# impulse.net
KiCad netlist of a schematic drawn in EAGLE
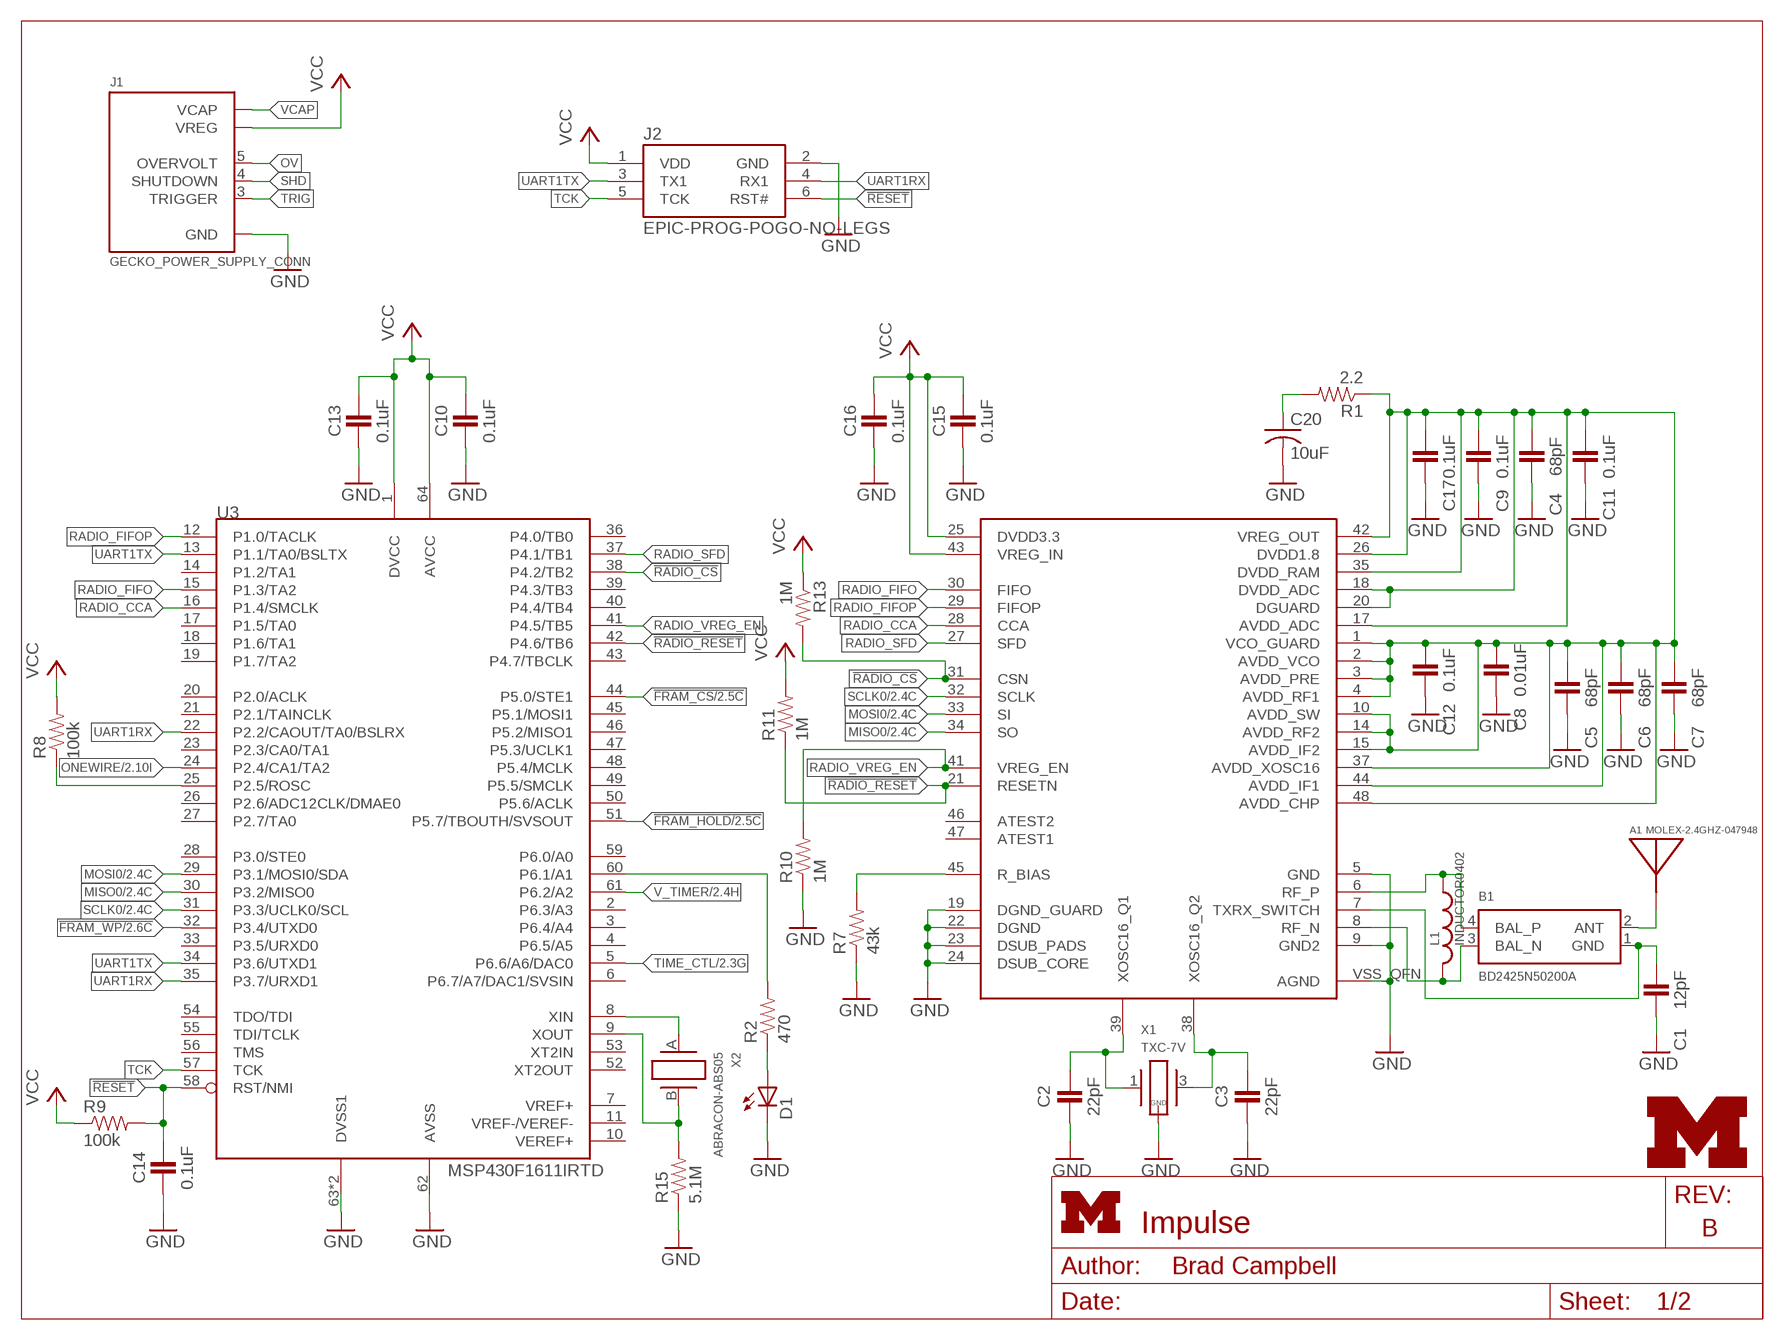
[diagram p0: schematic, sheet 1]
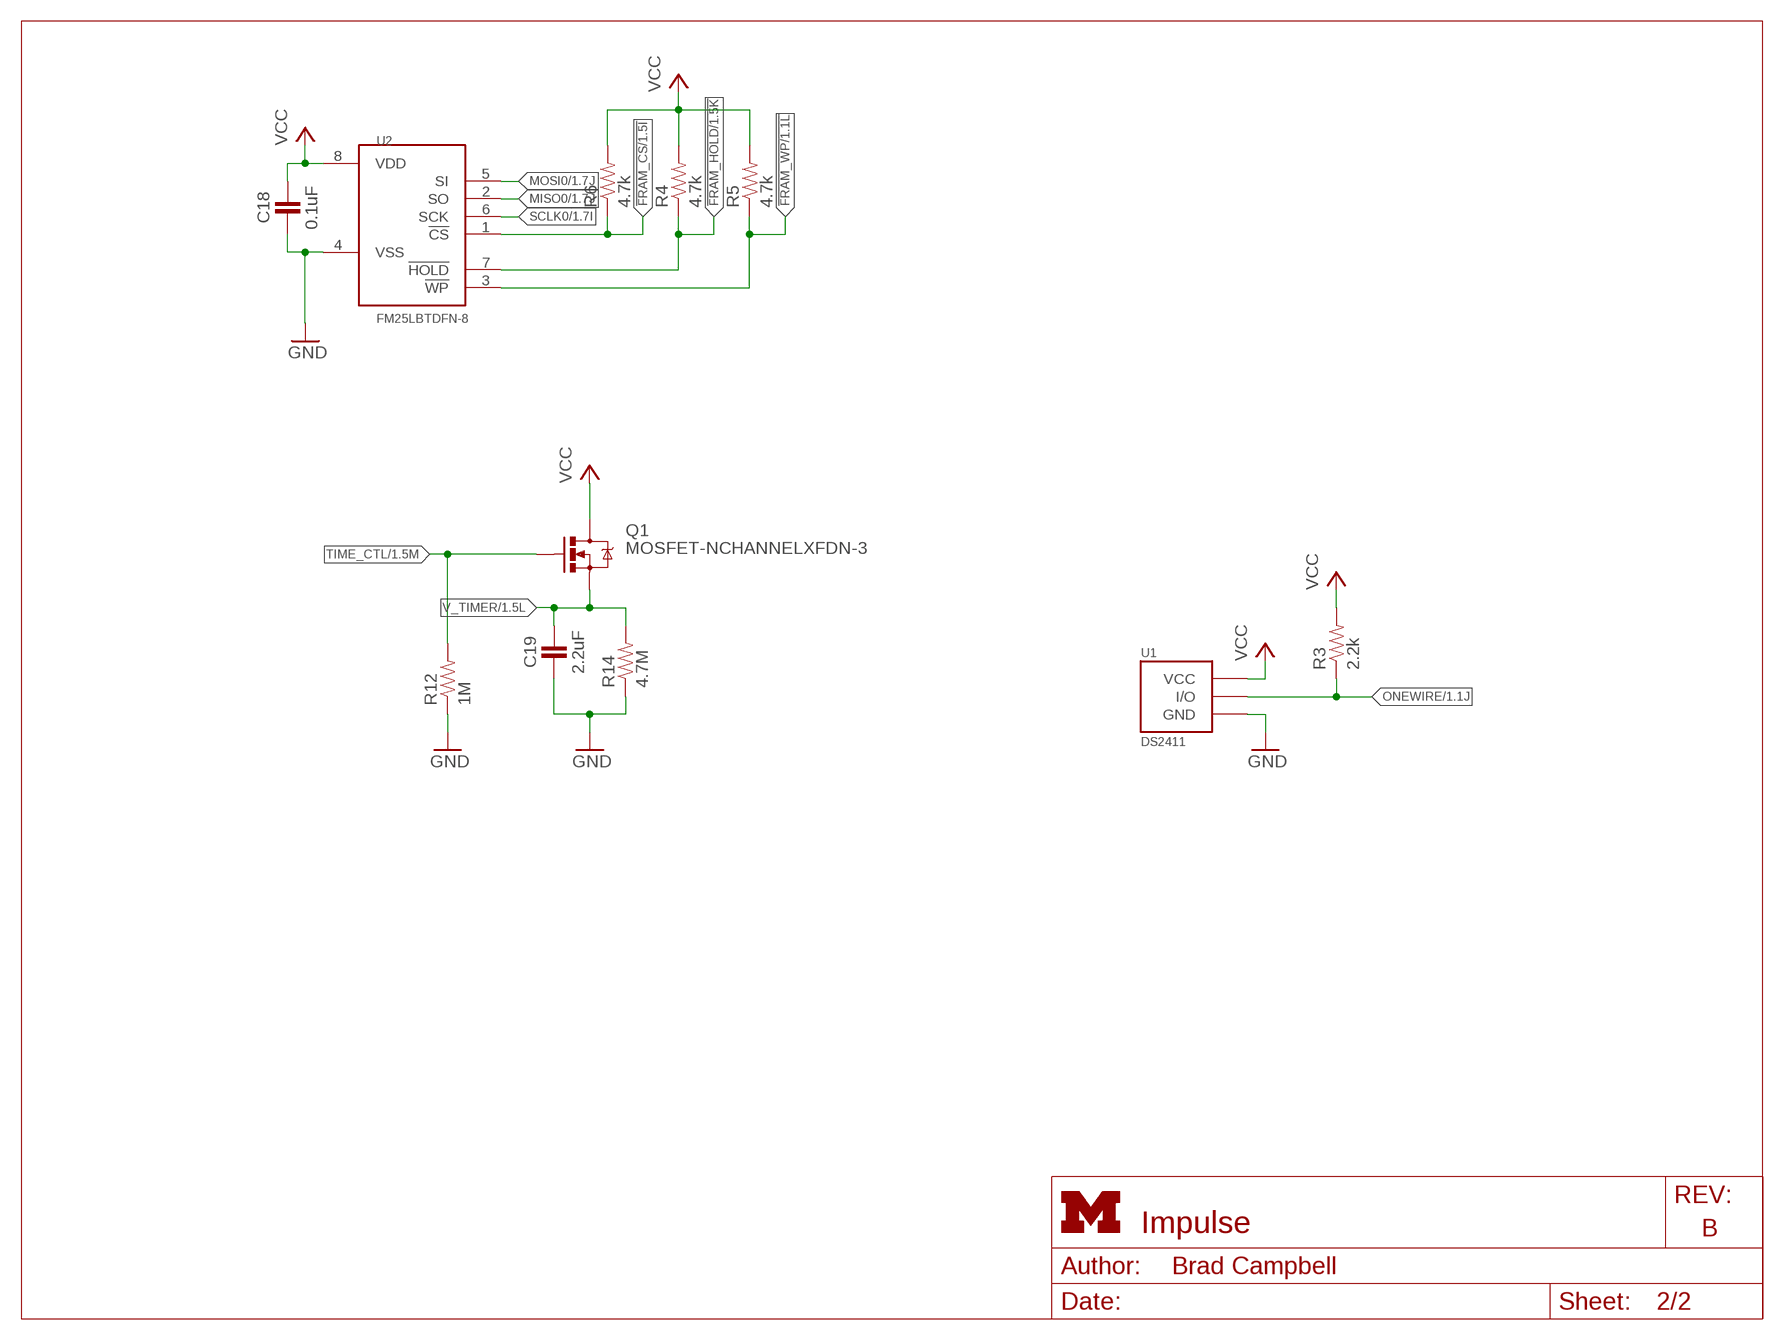
[diagram p1: schematic, sheet 2]

(export (version "E")
  (design (tool "Eeschema 10.0.6"))
  (components
    (comp (ref "C18")
      (value "0.1uF")
      (footprint "eagle-import:0402_CAP")
      (libsource (lib "eagle-import") (part "CAPACITOR"))
    )
    (comp (ref "C19")
      (value "2.2uF")
      (footprint "eagle-import:0402_CAP")
      (libsource (lib "eagle-import") (part "CAPACITOR"))
    )
    (comp (ref "Q1")
      (value "MOSFET-NCHANNELXFDN-3")
      (footprint "eagle-import:XFDFN-3")
      (libsource (lib "eagle-import") (part "MOSFET-NCHANNELXFDN-3"))
    )
    (comp (ref "R3")
      (value "2.2k")
      (footprint "eagle-import:0402_RES")
      (libsource (lib "eagle-import") (part "RESISTOR"))
    )
    (comp (ref "R4")
      (value "4.7k")
      (footprint "eagle-import:0402_RES")
      (libsource (lib "eagle-import") (part "RESISTOR"))
    )
    (comp (ref "R5")
      (value "4.7k")
      (footprint "eagle-import:0402_RES")
      (libsource (lib "eagle-import") (part "RESISTOR"))
    )
    (comp (ref "R6")
      (value "4.7k")
      (footprint "eagle-import:0402_RES")
      (libsource (lib "eagle-import") (part "RESISTOR"))
    )
    (comp (ref "R12")
      (value "1M")
      (footprint "eagle-import:0402_RES")
      (libsource (lib "eagle-import") (part "RESISTOR"))
    )
    (comp (ref "R14")
      (value "4.7M")
      (footprint "eagle-import:0402_RES")
      (libsource (lib "eagle-import") (part "RESISTOR"))
    )
    (comp (ref "U1")
      (value "DS2411")
      (footprint "eagle-import:SOT-23")
      (libsource (lib "eagle-import") (part "DS2411"))
    )
    (comp (ref "U2")
      (value "FM25LBTDFN-8")
      (footprint "eagle-import:TDFN-8")
      (libsource (lib "eagle-import") (part "FM25LBTDFN-8"))
    )
    (comp (ref "A1")
      (value "MOLEX-2.4GHZ-047948")
      (footprint "eagle-import:MOLEX-47948-ANTENNA")
      (libsource (lib "eagle-import") (part "MOLEX-2.4GHZ-047948"))
    )
    (comp (ref "B1")
      (value "BD2425N50200A")
      (footprint "eagle-import:BD2425N50200A")
      (libsource (lib "eagle-import") (part "BD2425N50200A"))
    )
    (comp (ref "C1")
      (value "12pF")
      (footprint "eagle-import:0402_CAP")
      (libsource (lib "eagle-import") (part "CAPACITOR"))
    )
    (comp (ref "C2")
      (value "22pF")
      (footprint "eagle-import:0402_CAP")
      (libsource (lib "eagle-import") (part "CAPACITOR"))
    )
    (comp (ref "C3")
      (value "22pF")
      (footprint "eagle-import:0402_CAP")
      (libsource (lib "eagle-import") (part "CAPACITOR"))
    )
    (comp (ref "C4")
      (value "68pF")
      (footprint "eagle-import:0402_CAP")
      (libsource (lib "eagle-import") (part "CAPACITOR"))
    )
    (comp (ref "C5")
      (value "68pF")
      (footprint "eagle-import:0402_CAP")
      (libsource (lib "eagle-import") (part "CAPACITOR"))
    )
    (comp (ref "C6")
      (value "68pF")
      (footprint "eagle-import:0402_CAP")
      (libsource (lib "eagle-import") (part "CAPACITOR"))
    )
    (comp (ref "C7")
      (value "68pF")
      (footprint "eagle-import:0402_CAP")
      (libsource (lib "eagle-import") (part "CAPACITOR"))
    )
    (comp (ref "C8")
      (value "0.01uF")
      (footprint "eagle-import:0402_CAP")
      (libsource (lib "eagle-import") (part "CAPACITOR"))
    )
    (comp (ref "C9")
      (value "0.1uF")
      (footprint "eagle-import:0402_CAP")
      (libsource (lib "eagle-import") (part "CAPACITOR"))
    )
    (comp (ref "C10")
      (value "0.1uF")
      (footprint "eagle-import:0402_CAP")
      (libsource (lib "eagle-import") (part "CAPACITOR"))
    )
    (comp (ref "C11")
      (value "0.1uF")
      (footprint "eagle-import:0402_CAP")
      (libsource (lib "eagle-import") (part "CAPACITOR"))
    )
    (comp (ref "C12")
      (value "0.1uF")
      (footprint "eagle-import:0402_CAP")
      (libsource (lib "eagle-import") (part "CAPACITOR"))
    )
    (comp (ref "C13")
      (value "0.1uF")
      (footprint "eagle-import:0402_CAP")
      (libsource (lib "eagle-import") (part "CAPACITOR"))
    )
    (comp (ref "C14")
      (value "0.1uF")
      (footprint "eagle-import:0402_CAP")
      (libsource (lib "eagle-import") (part "CAPACITOR"))
    )
    (comp (ref "C15")
      (value "0.1uF")
      (footprint "eagle-import:0402_CAP")
      (libsource (lib "eagle-import") (part "CAPACITOR"))
    )
    (comp (ref "C16")
      (value "0.1uF")
      (footprint "eagle-import:0402_CAP")
      (libsource (lib "eagle-import") (part "CAPACITOR"))
    )
    (comp (ref "C17")
      (value "0.1uF")
      (footprint "eagle-import:0402_CAP")
      (libsource (lib "eagle-import") (part "CAPACITOR"))
    )
    (comp (ref "C20")
      (value "10uF")
      (footprint "eagle-import:C0805")
      (libsource (lib "eagle-import") (part "C-USC0805"))
    )
    (comp (ref "D1")
      (value "LED0603")
      (footprint "eagle-import:LED-0603")
      (libsource (lib "eagle-import") (part "LED0603"))
    )
    (comp (ref "J1")
      (value "GECKO_POWER_SUPPLY_CONN")
      (footprint "eagle-import:HEADER1X6_0.05IN")
      (libsource (lib "eagle-import") (part "GECKO_POWER_SUPPLY_CONN"))
    )
    (comp (ref "J2")
      (value "EPIC-PROG-POGO-NO-LEGS")
      (footprint "eagle-import:TC2030-IDC-NL")
      (libsource (lib "eagle-import") (part "EPIC-PROG-POGO-NO-LEGS"))
    )
    (comp (ref "L1")
      (value "INDUCTOR0402")
      (footprint "eagle-import:0402_CAP")
      (libsource (lib "eagle-import") (part "INDUCTOR0402"))
    )
    (comp (ref "R1")
      (value "2.2")
      (footprint "eagle-import:0402_RES")
      (libsource (lib "eagle-import") (part "RESISTOR"))
    )
    (comp (ref "R2")
      (value "470")
      (footprint "eagle-import:0402_RES")
      (libsource (lib "eagle-import") (part "RESISTOR"))
    )
    (comp (ref "R7")
      (value "43k")
      (footprint "eagle-import:0402_RES")
      (libsource (lib "eagle-import") (part "RESISTOR"))
    )
    (comp (ref "R8")
      (value "100k")
      (footprint "eagle-import:0402_RES")
      (libsource (lib "eagle-import") (part "RESISTOR"))
    )
    (comp (ref "R9")
      (value "100k")
      (footprint "eagle-import:0402_RES")
      (libsource (lib "eagle-import") (part "RESISTOR"))
    )
    (comp (ref "R10")
      (value "1M")
      (footprint "eagle-import:0402_RES")
      (libsource (lib "eagle-import") (part "RESISTOR"))
    )
    (comp (ref "R11")
      (value "1M")
      (footprint "eagle-import:0402_RES")
      (libsource (lib "eagle-import") (part "RESISTOR"))
    )
    (comp (ref "R13")
      (value "1M")
      (footprint "eagle-import:0402_RES")
      (libsource (lib "eagle-import") (part "RESISTOR"))
    )
    (comp (ref "R15")
      (value "5.1M")
      (footprint "eagle-import:0402_RES")
      (libsource (lib "eagle-import") (part "RESISTOR"))
    )
    (comp (ref "U$1")
      (value "UMICH_SOLID_SMALL")
      (footprint "eagle-import:UMICH_SOLID_75MIL")
      (libsource (lib "eagle-import") (part "UMICH_SOLID_SMALL"))
    )
    (comp (ref "U3")
      (value "MSP430F1611IRTD")
      (footprint "eagle-import:S-PVQFN-N64")
      (libsource (lib "eagle-import") (part "MSP430F1611IRTD"))
    )
    (comp (ref "U4")
      (value "CC2420RGZ")
      (footprint "eagle-import:S-PVQFN-N48")
      (libsource (lib "eagle-import") (part "CC2420RGZ"))
    )
    (comp (ref "X1")
      (value "TXC-7V")
      (footprint "eagle-import:TXC-7V")
      (libsource (lib "eagle-import") (part "TXC-7V"))
    )
    (comp (ref "X2")
      (value "ABRACON-ABS05")
      (footprint "eagle-import:ABS05")
      (libsource (lib "eagle-import") (part "ABRACON-ABS05"))
    )
  )
  (nets
    (net (code "1") (name "GND") (class "Default")
      (node (ref "C1") (pin "2") (pinfunction "2_2") (pintype "bidirectional"))
      (node (ref "C10") (pin "2") (pinfunction "2_2") (pintype "bidirectional"))
      (node (ref "C11") (pin "2") (pinfunction "2_2") (pintype "bidirectional"))
      (node (ref "C12") (pin "2") (pinfunction "2_2") (pintype "bidirectional"))
      (node (ref "C13") (pin "2") (pinfunction "2_2") (pintype "bidirectional"))
      (node (ref "C14") (pin "2") (pinfunction "2_2") (pintype "bidirectional"))
      (node (ref "C15") (pin "2") (pinfunction "2_2") (pintype "bidirectional"))
      (node (ref "C16") (pin "2") (pinfunction "2_2") (pintype "bidirectional"))
      (node (ref "C17") (pin "2") (pinfunction "2_2") (pintype "bidirectional"))
      (node (ref "C18") (pin "2") (pinfunction "2_2") (pintype "bidirectional"))
      (node (ref "C19") (pin "2") (pinfunction "2_2") (pintype "bidirectional"))
      (node (ref "C2") (pin "2") (pinfunction "2_2") (pintype "bidirectional"))
      (node (ref "C20") (pin "2") (pinfunction "2_2") (pintype "passive"))
      (node (ref "C3") (pin "2") (pinfunction "2_2") (pintype "bidirectional"))
      (node (ref "C4") (pin "2") (pinfunction "2_2") (pintype "bidirectional"))
      (node (ref "C5") (pin "2") (pinfunction "2_2") (pintype "bidirectional"))
      (node (ref "C6") (pin "2") (pinfunction "2_2") (pintype "bidirectional"))
      (node (ref "C7") (pin "2") (pinfunction "2_2") (pintype "bidirectional"))
      (node (ref "C8") (pin "2") (pinfunction "2_2") (pintype "bidirectional"))
      (node (ref "C9") (pin "2") (pinfunction "2_2") (pintype "bidirectional"))
      (node (ref "D1") (pin "C") (pinfunction "C_C") (pintype "passive"))
      (node (ref "J1") (pin "1") (pinfunction "GND_1") (pintype "bidirectional"))
      (node (ref "J2") (pin "2") (pinfunction "GND_2") (pintype "bidirectional"))
      (node (ref "R10") (pin "1") (pinfunction "1_1") (pintype "passive"))
      (node (ref "R12") (pin "1") (pinfunction "1_1") (pintype "passive"))
      (node (ref "R14") (pin "1") (pinfunction "1_1") (pintype "passive"))
      (node (ref "R15") (pin "1") (pinfunction "1_1") (pintype "passive"))
      (node (ref "R7") (pin "1") (pinfunction "1_1") (pintype "passive"))
      (node (ref "U1") (pin "3") (pinfunction "GND_3") (pintype "bidirectional"))
      (node (ref "U2") (pin "4") (pinfunction "VSS_4") (pintype "bidirectional"))
      (node (ref "U3") (pin "62") (pinfunction "AVSS_62") (pintype "power_in"))
      (node (ref "U3") (pin "63") (pinfunction "DVSS1_63") (pintype "power_in"))
      (node (ref "U3") (pin "GND") (pinfunction "DVSS1_GND") (pintype "power_in"))
      (node (ref "U4") (pin "19") (pinfunction "DGND_GUARD_19") (pintype "bidirectional"))
      (node (ref "U4") (pin "22") (pinfunction "DGND_22") (pintype "bidirectional"))
      (node (ref "U4") (pin "23") (pinfunction "DSUB_PADS_23") (pintype "bidirectional"))
      (node (ref "U4") (pin "24") (pinfunction "DSUB_CORE_24") (pintype "bidirectional"))
      (node (ref "U4") (pin "5") (pinfunction "GND_5") (pintype "bidirectional"))
      (node (ref "U4") (pin "9") (pinfunction "GND2_9") (pintype "bidirectional"))
      (node (ref "U4") (pin "VSS_QFN") (pinfunction "AGND_VSS_QFN") (pintype "bidirectional"))
      (node (ref "X1") (pin "2") (pinfunction "GND_2") (pintype "bidirectional"))
      (node (ref "X1") (pin "4") (pinfunction "GND_4") (pintype "bidirectional"))
    )
    (net (code "2") (name "MISO0") (class "Default")
      (node (ref "U2") (pin "2") (pinfunction "SO_2") (pintype "bidirectional"))
      (node (ref "U3") (pin "30") (pinfunction "P3.2/MISO0_30") (pintype "bidirectional"))
      (node (ref "U4") (pin "34") (pinfunction "SO_34") (pintype "bidirectional"))
    )
    (net (code "3") (name "MOSI0") (class "Default")
      (node (ref "U2") (pin "5") (pinfunction "SI_5") (pintype "bidirectional"))
      (node (ref "U3") (pin "29") (pinfunction "P3.1/MOSI0/SDA_29") (pintype "bidirectional"))
      (node (ref "U4") (pin "33") (pinfunction "SI_33") (pintype "bidirectional"))
    )
    (net (code "4") (name "Net-(A1-ANTENNA)") (class "Default")
      (node (ref "A1") (pin "1") (pinfunction "ANTENNA_1") (pintype "bidirectional"))
      (node (ref "B1") (pin "2") (pinfunction "ANT_2") (pintype "bidirectional"))
    )
    (net (code "5") (name "Net-(B1-BAL_N)") (class "Default")
      (node (ref "B1") (pin "3") (pinfunction "BAL_N_3") (pintype "bidirectional"))
      (node (ref "L1") (pin "2") (pinfunction "P$2_2") (pintype "bidirectional"))
      (node (ref "U4") (pin "8") (pinfunction "RF_N_8") (pintype "bidirectional"))
    )
    (net (code "6") (name "Net-(B1-BAL_P)") (class "Default")
      (node (ref "B1") (pin "4") (pinfunction "BAL_P_4") (pintype "bidirectional"))
      (node (ref "L1") (pin "1") (pinfunction "1_1") (pintype "bidirectional"))
      (node (ref "U4") (pin "6") (pinfunction "RF_P_6") (pintype "bidirectional"))
    )
    (net (code "7") (name "Net-(B1-GND)") (class "Default")
      (node (ref "B1") (pin "1") (pinfunction "GND_1") (pintype "bidirectional"))
      (node (ref "C1") (pin "1") (pinfunction "1_1") (pintype "bidirectional"))
      (node (ref "U4") (pin "7") (pinfunction "TXRX_SWITCH_7") (pintype "bidirectional"))
    )
    (net (code "8") (name "Net-(C20-Pad1)") (class "Default")
      (node (ref "C20") (pin "1") (pinfunction "1_1") (pintype "passive"))
      (node (ref "R1") (pin "2") (pinfunction "2_2") (pintype "passive"))
    )
    (net (code "9") (name "Net-(D1-PadA)") (class "Default")
      (node (ref "D1") (pin "A") (pinfunction "A_A") (pintype "passive"))
      (node (ref "R2") (pin "1") (pinfunction "1_1") (pintype "passive"))
    )
    (net (code "10") (name "Net-(U3-P2.5{slash}ROSC)") (class "Default")
      (node (ref "R8") (pin "1") (pinfunction "1_1") (pintype "passive"))
      (node (ref "U3") (pin "25") (pinfunction "P2.5/ROSC_25") (pintype "bidirectional"))
    )
    (net (code "11") (name "Net-(U3-P6.1{slash}A1)") (class "Default")
      (node (ref "R2") (pin "2") (pinfunction "2_2") (pintype "passive"))
      (node (ref "U3") (pin "60") (pinfunction "P6.1/A1_60") (pintype "bidirectional"))
    )
    (net (code "12") (name "Net-(U3-XIN)") (class "Default")
      (node (ref "U3") (pin "8") (pinfunction "XIN_8") (pintype "bidirectional"))
      (node (ref "X2") (pin "A") (pinfunction "1_A") (pintype "bidirectional"))
    )
    (net (code "13") (name "Net-(U3-XOUT)") (class "Default")
      (node (ref "R15") (pin "2") (pinfunction "2_2") (pintype "passive"))
      (node (ref "U3") (pin "9") (pinfunction "XOUT_9") (pintype "bidirectional"))
      (node (ref "X2") (pin "B") (pinfunction "2_B") (pintype "bidirectional"))
    )
    (net (code "14") (name "Net-(U4-AVDD_ADC)") (class "Default")
      (node (ref "C11") (pin "1") (pinfunction "1_1") (pintype "bidirectional"))
      (node (ref "C12") (pin "1") (pinfunction "1_1") (pintype "bidirectional"))
      (node (ref "C17") (pin "1") (pinfunction "1_1") (pintype "bidirectional"))
      (node (ref "C4") (pin "1") (pinfunction "1_1") (pintype "bidirectional"))
      (node (ref "C5") (pin "1") (pinfunction "1_1") (pintype "bidirectional"))
      (node (ref "C6") (pin "1") (pinfunction "1_1") (pintype "bidirectional"))
      (node (ref "C7") (pin "1") (pinfunction "1_1") (pintype "bidirectional"))
      (node (ref "C8") (pin "1") (pinfunction "1_1") (pintype "bidirectional"))
      (node (ref "C9") (pin "1") (pinfunction "1_1") (pintype "bidirectional"))
      (node (ref "R1") (pin "1") (pinfunction "1_1") (pintype "passive"))
      (node (ref "U4") (pin "1") (pinfunction "VCO_GUARD_1") (pintype "bidirectional"))
      (node (ref "U4") (pin "10") (pinfunction "AVDD_SW_10") (pintype "bidirectional"))
      (node (ref "U4") (pin "14") (pinfunction "AVDD_RF2_14") (pintype "bidirectional"))
      (node (ref "U4") (pin "15") (pinfunction "AVDD_IF2_15") (pintype "bidirectional"))
      (node (ref "U4") (pin "17") (pinfunction "AVDD_ADC_17") (pintype "bidirectional"))
      (node (ref "U4") (pin "18") (pinfunction "DVDD_ADC_18") (pintype "bidirectional"))
      (node (ref "U4") (pin "2") (pinfunction "AVDD_VCO_2") (pintype "bidirectional"))
      (node (ref "U4") (pin "20") (pinfunction "DGUARD_20") (pintype "bidirectional"))
      (node (ref "U4") (pin "26") (pinfunction "DVDD1.8_26") (pintype "bidirectional"))
      (node (ref "U4") (pin "3") (pinfunction "AVDD_PRE_3") (pintype "bidirectional"))
      (node (ref "U4") (pin "35") (pinfunction "DVDD_RAM_35") (pintype "bidirectional"))
      (node (ref "U4") (pin "37") (pinfunction "AVDD_XOSC16_37") (pintype "bidirectional"))
      (node (ref "U4") (pin "4") (pinfunction "AVDD_RF1_4") (pintype "bidirectional"))
      (node (ref "U4") (pin "42") (pinfunction "VREG_OUT_42") (pintype "bidirectional"))
      (node (ref "U4") (pin "44") (pinfunction "AVDD_IF1_44") (pintype "bidirectional"))
      (node (ref "U4") (pin "48") (pinfunction "AVDD_CHP_48") (pintype "bidirectional"))
    )
    (net (code "15") (name "Net-(U4-R_BIAS)") (class "Default")
      (node (ref "R7") (pin "2") (pinfunction "2_2") (pintype "passive"))
      (node (ref "U4") (pin "45") (pinfunction "R_BIAS_45") (pintype "bidirectional"))
    )
    (net (code "16") (name "Net-(U4-XOSC16_Q1)") (class "Default")
      (node (ref "C2") (pin "1") (pinfunction "1_1") (pintype "bidirectional"))
      (node (ref "U4") (pin "39") (pinfunction "XOSC16_Q1_39") (pintype "bidirectional"))
      (node (ref "X1") (pin "1") (pinfunction "1_1") (pintype "bidirectional"))
    )
    (net (code "17") (name "Net-(U4-XOSC16_Q2)") (class "Default")
      (node (ref "C3") (pin "1") (pinfunction "1_1") (pintype "bidirectional"))
      (node (ref "U4") (pin "38") (pinfunction "XOSC16_Q2_38") (pintype "bidirectional"))
      (node (ref "X1") (pin "3") (pinfunction "2_3") (pintype "bidirectional"))
    )
    (net (code "18") (name "ONEWIRE") (class "Default")
      (node (ref "R3") (pin "1") (pinfunction "1_1") (pintype "passive"))
      (node (ref "U1") (pin "1") (pinfunction "I/O_1") (pintype "bidirectional"))
      (node (ref "U3") (pin "24") (pinfunction "P2.4/CA1/TA2_24") (pintype "bidirectional"))
    )
    (net (code "19") (name "OV") (class "Default")
      (node (ref "J1") (pin "5") (pinfunction "OVERVOLT_5") (pintype "bidirectional"))
    )
    (net (code "20") (name "RADIO_CCA") (class "Default")
      (node (ref "U3") (pin "16") (pinfunction "P1.4/SMCLK_16") (pintype "bidirectional"))
      (node (ref "U4") (pin "28") (pinfunction "CCA_28") (pintype "bidirectional"))
    )
    (net (code "21") (name "RADIO_FIFO") (class "Default")
      (node (ref "U3") (pin "15") (pinfunction "P1.3/TA2_15") (pintype "bidirectional"))
      (node (ref "U4") (pin "30") (pinfunction "FIFO_30") (pintype "bidirectional"))
    )
    (net (code "22") (name "RADIO_FIFOP") (class "Default")
      (node (ref "U3") (pin "12") (pinfunction "P1.0/TACLK_12") (pintype "bidirectional"))
      (node (ref "U4") (pin "29") (pinfunction "FIFOP_29") (pintype "bidirectional"))
    )
    (net (code "23") (name "RADIO_SFD") (class "Default")
      (node (ref "U3") (pin "37") (pinfunction "P4.1/TB1_37") (pintype "bidirectional"))
      (node (ref "U4") (pin "27") (pinfunction "SFD_27") (pintype "bidirectional"))
    )
    (net (code "24") (name "RADIO_VREG_EN") (class "Default")
      (node (ref "R10") (pin "2") (pinfunction "2_2") (pintype "passive"))
      (node (ref "U3") (pin "41") (pinfunction "P4.5/TB5_41") (pintype "bidirectional"))
      (node (ref "U4") (pin "41") (pinfunction "VREG_EN_41") (pintype "bidirectional"))
    )
    (net (code "25") (name "SCLK0") (class "Default")
      (node (ref "U2") (pin "6") (pinfunction "SCK_6") (pintype "bidirectional"))
      (node (ref "U3") (pin "31") (pinfunction "P3.3/UCLK0/SCL_31") (pintype "bidirectional"))
      (node (ref "U4") (pin "32") (pinfunction "SCLK_32") (pintype "bidirectional"))
    )
    (net (code "26") (name "SHD") (class "Default")
      (node (ref "J1") (pin "4") (pinfunction "SHUTDOWN_4") (pintype "bidirectional"))
    )
    (net (code "27") (name "TCK") (class "Default")
      (node (ref "J2") (pin "5") (pinfunction "TCK_5") (pintype "bidirectional"))
      (node (ref "U3") (pin "57") (pinfunction "TCK_57") (pintype "bidirectional"))
    )
    (net (code "28") (name "TIME_CTL") (class "Default")
      (node (ref "Q1") (pin "G") (pinfunction "G_G") (pintype "passive"))
      (node (ref "R12") (pin "2") (pinfunction "2_2") (pintype "passive"))
      (node (ref "U3") (pin "5") (pinfunction "P6.6/A6/DAC0_5") (pintype "bidirectional"))
    )
    (net (code "29") (name "TRIG") (class "Default")
      (node (ref "J1") (pin "3") (pinfunction "TRIGGER_3") (pintype "bidirectional"))
    )
    (net (code "30") (name "UART1RX") (class "Default")
      (node (ref "J2") (pin "4") (pinfunction "RX1_4") (pintype "bidirectional"))
      (node (ref "U3") (pin "22") (pinfunction "P2.2/CAOUT/TA0/BSLRX_22") (pintype "bidirectional"))
      (node (ref "U3") (pin "35") (pinfunction "P3.7/URXD1_35") (pintype "bidirectional"))
    )
    (net (code "31") (name "UART1TX") (class "Default")
      (node (ref "J2") (pin "3") (pinfunction "TX1_3") (pintype "bidirectional"))
      (node (ref "U3") (pin "13") (pinfunction "P1.1/TA0/BSLTX_13") (pintype "bidirectional"))
      (node (ref "U3") (pin "34") (pinfunction "P3.6/UTXD1_34") (pintype "bidirectional"))
    )
    (net (code "32") (name "VCAP") (class "Default")
      (node (ref "J1") (pin "6") (pinfunction "VCAP_6") (pintype "output"))
    )
    (net (code "33") (name "VCC") (class "Default")
      (node (ref "C10") (pin "1") (pinfunction "1_1") (pintype "bidirectional"))
      (node (ref "C13") (pin "1") (pinfunction "1_1") (pintype "bidirectional"))
      (node (ref "C15") (pin "1") (pinfunction "1_1") (pintype "bidirectional"))
      (node (ref "C16") (pin "1") (pinfunction "1_1") (pintype "bidirectional"))
      (node (ref "C18") (pin "1") (pinfunction "1_1") (pintype "bidirectional"))
      (node (ref "J1") (pin "2") (pinfunction "VREG_2") (pintype "bidirectional"))
      (node (ref "J2") (pin "1") (pinfunction "VDD_1") (pintype "bidirectional"))
      (node (ref "Q1") (pin "D") (pinfunction "D_D") (pintype "passive"))
      (node (ref "R11") (pin "2") (pinfunction "2_2") (pintype "passive"))
      (node (ref "R13") (pin "1") (pinfunction "1_1") (pintype "passive"))
      (node (ref "R3") (pin "2") (pinfunction "2_2") (pintype "passive"))
      (node (ref "R4") (pin "2") (pinfunction "2_2") (pintype "passive"))
      (node (ref "R5") (pin "2") (pinfunction "2_2") (pintype "passive"))
      (node (ref "R6") (pin "2") (pinfunction "2_2") (pintype "passive"))
      (node (ref "R8") (pin "2") (pinfunction "2_2") (pintype "passive"))
      (node (ref "R9") (pin "1") (pinfunction "1_1") (pintype "passive"))
      (node (ref "U1") (pin "2") (pinfunction "VCC_2") (pintype "bidirectional"))
      (node (ref "U2") (pin "8") (pinfunction "VDD_8") (pintype "bidirectional"))
      (node (ref "U3") (pin "1") (pinfunction "DVCC_1") (pintype "power_in"))
      (node (ref "U3") (pin "64") (pinfunction "AVCC_64") (pintype "power_in"))
      (node (ref "U4") (pin "25") (pinfunction "DVDD3.3_25") (pintype "bidirectional"))
      (node (ref "U4") (pin "43") (pinfunction "VREG_IN_43") (pintype "bidirectional"))
    )
    (net (code "34") (name "V_TIMER") (class "Default")
      (node (ref "C19") (pin "1") (pinfunction "1_1") (pintype "bidirectional"))
      (node (ref "Q1") (pin "S") (pinfunction "S_S") (pintype "passive"))
      (node (ref "R14") (pin "2") (pinfunction "2_2") (pintype "passive"))
      (node (ref "U3") (pin "61") (pinfunction "P6.2/A2_61") (pintype "bidirectional"))
    )
    (net (code "35") (name "unconnected-(U3-P1.2{slash}TA1-Pad14)") (class "Default")
      (node (ref "U3") (pin "14") (pinfunction "P1.2/TA1_14") (pintype "bidirectional"))
    )
    (net (code "36") (name "unconnected-(U3-P1.5{slash}TA0-Pad17)") (class "Default")
      (node (ref "U3") (pin "17") (pinfunction "P1.5/TA0_17") (pintype "bidirectional"))
    )
    (net (code "37") (name "unconnected-(U3-P1.6{slash}TA1-Pad18)") (class "Default")
      (node (ref "U3") (pin "18") (pinfunction "P1.6/TA1_18") (pintype "bidirectional"))
    )
    (net (code "38") (name "unconnected-(U3-P1.7{slash}TA2-Pad19)") (class "Default")
      (node (ref "U3") (pin "19") (pinfunction "P1.7/TA2_19") (pintype "bidirectional"))
    )
    (net (code "39") (name "unconnected-(U3-P2.0{slash}ACLK-Pad20)") (class "Default")
      (node (ref "U3") (pin "20") (pinfunction "P2.0/ACLK_20") (pintype "bidirectional"))
    )
    (net (code "40") (name "unconnected-(U3-P2.1{slash}TAINCLK-Pad21)") (class "Default")
      (node (ref "U3") (pin "21") (pinfunction "P2.1/TAINCLK_21") (pintype "bidirectional"))
    )
    (net (code "41") (name "unconnected-(U3-P2.3{slash}CA0{slash}TA1-Pad23)") (class "Default")
      (node (ref "U3") (pin "23") (pinfunction "P2.3/CA0/TA1_23") (pintype "bidirectional"))
    )
    (net (code "42") (name "unconnected-(U3-P2.6{slash}ADC12CLK{slash}DMAE0-Pad26)") (class "Default")
      (node (ref "U3") (pin "26") (pinfunction "P2.6/ADC12CLK/DMAE0_26") (pintype "bidirectional"))
    )
    (net (code "43") (name "unconnected-(U3-P2.7{slash}TA0-Pad27)") (class "Default")
      (node (ref "U3") (pin "27") (pinfunction "P2.7/TA0_27") (pintype "bidirectional"))
    )
    (net (code "44") (name "unconnected-(U3-P3.0{slash}STE0-Pad28)") (class "Default")
      (node (ref "U3") (pin "28") (pinfunction "P3.0/STE0_28") (pintype "bidirectional"))
    )
    (net (code "45") (name "unconnected-(U3-P3.5{slash}URXD0-Pad33)") (class "Default")
      (node (ref "U3") (pin "33") (pinfunction "P3.5/URXD0_33") (pintype "bidirectional"))
    )
    (net (code "46") (name "unconnected-(U3-P4.0{slash}TB0-Pad36)") (class "Default")
      (node (ref "U3") (pin "36") (pinfunction "P4.0/TB0_36") (pintype "bidirectional"))
    )
    (net (code "47") (name "unconnected-(U3-P4.3{slash}TB3-Pad39)") (class "Default")
      (node (ref "U3") (pin "39") (pinfunction "P4.3/TB3_39") (pintype "bidirectional"))
    )
    (net (code "48") (name "unconnected-(U3-P4.4{slash}TB4-Pad40)") (class "Default")
      (node (ref "U3") (pin "40") (pinfunction "P4.4/TB4_40") (pintype "bidirectional"))
    )
    (net (code "49") (name "unconnected-(U3-P4.7{slash}TBCLK-Pad43)") (class "Default")
      (node (ref "U3") (pin "43") (pinfunction "P4.7/TBCLK_43") (pintype "bidirectional"))
    )
    (net (code "50") (name "unconnected-(U3-P5.1{slash}MOSI1-Pad45)") (class "Default")
      (node (ref "U3") (pin "45") (pinfunction "P5.1/MOSI1_45") (pintype "bidirectional"))
    )
    (net (code "51") (name "unconnected-(U3-P5.2{slash}MISO1-Pad46)") (class "Default")
      (node (ref "U3") (pin "46") (pinfunction "P5.2/MISO1_46") (pintype "bidirectional"))
    )
    (net (code "52") (name "unconnected-(U3-P5.3{slash}UCLK1-Pad47)") (class "Default")
      (node (ref "U3") (pin "47") (pinfunction "P5.3/UCLK1_47") (pintype "bidirectional"))
    )
    (net (code "53") (name "unconnected-(U3-P5.4{slash}MCLK-Pad48)") (class "Default")
      (node (ref "U3") (pin "48") (pinfunction "P5.4/MCLK_48") (pintype "bidirectional"))
    )
    (net (code "54") (name "unconnected-(U3-P5.5{slash}SMCLK-Pad49)") (class "Default")
      (node (ref "U3") (pin "49") (pinfunction "P5.5/SMCLK_49") (pintype "bidirectional"))
    )
    (net (code "55") (name "unconnected-(U3-P5.6{slash}ACLK-Pad50)") (class "Default")
      (node (ref "U3") (pin "50") (pinfunction "P5.6/ACLK_50") (pintype "bidirectional"))
    )
    (net (code "56") (name "unconnected-(U3-P6.0{slash}A0-Pad59)") (class "Default")
      (node (ref "U3") (pin "59") (pinfunction "P6.0/A0_59") (pintype "bidirectional"))
    )
    (net (code "57") (name "unconnected-(U3-P6.3{slash}A3-Pad2)") (class "Default")
      (node (ref "U3") (pin "2") (pinfunction "P6.3/A3_2") (pintype "bidirectional"))
    )
    (net (code "58") (name "unconnected-(U3-P6.4{slash}A4-Pad3)") (class "Default")
      (node (ref "U3") (pin "3") (pinfunction "P6.4/A4_3") (pintype "bidirectional"))
    )
    (net (code "59") (name "unconnected-(U3-P6.5{slash}A5-Pad4)") (class "Default")
      (node (ref "U3") (pin "4") (pinfunction "P6.5/A5_4") (pintype "bidirectional"))
    )
    (net (code "60") (name "unconnected-(U3-P6.7{slash}A7{slash}DAC1{slash}SVSIN-Pad6)") (class "Default")
      (node (ref "U3") (pin "6") (pinfunction "P6.7/A7/DAC1/SVSIN_6") (pintype "bidirectional"))
    )
    (net (code "61") (name "unconnected-(U3-TDI{slash}TCLK-Pad55)") (class "Default")
      (node (ref "U3") (pin "55") (pinfunction "TDI/TCLK_55") (pintype "bidirectional"))
    )
    (net (code "62") (name "unconnected-(U3-TDO{slash}TDI-Pad54)") (class "Default")
      (node (ref "U3") (pin "54") (pinfunction "TDO/TDI_54") (pintype "bidirectional"))
    )
    (net (code "63") (name "unconnected-(U3-TMS-Pad56)") (class "Default")
      (node (ref "U3") (pin "56") (pinfunction "TMS_56") (pintype "bidirectional"))
    )
    (net (code "64") (name "unconnected-(U3-VEREF+-Pad10)") (class "Default")
      (node (ref "U3") (pin "10") (pinfunction "VEREF+_10") (pintype "bidirectional"))
    )
    (net (code "65") (name "unconnected-(U3-VREF+-Pad7)") (class "Default")
      (node (ref "U3") (pin "7") (pinfunction "VREF+_7") (pintype "bidirectional"))
    )
    (net (code "66") (name "unconnected-(U3-VREF-{slash}VEREF--Pad11)") (class "Default")
      (node (ref "U3") (pin "11") (pinfunction "VREF-/VEREF-_11") (pintype "bidirectional"))
    )
    (net (code "67") (name "unconnected-(U3-XT2IN-Pad53)") (class "Default")
      (node (ref "U3") (pin "53") (pinfunction "XT2IN_53") (pintype "bidirectional"))
    )
    (net (code "68") (name "unconnected-(U3-XT2OUT-Pad52)") (class "Default")
      (node (ref "U3") (pin "52") (pinfunction "XT2OUT_52") (pintype "bidirectional"))
    )
    (net (code "69") (name "unconnected-(U4-ATEST1-Pad47)") (class "Default")
      (node (ref "U4") (pin "47") (pinfunction "ATEST1_47") (pintype "bidirectional"))
    )
    (net (code "70") (name "unconnected-(U4-ATEST2-Pad46)") (class "Default")
      (node (ref "U4") (pin "46") (pinfunction "ATEST2_46") (pintype "bidirectional"))
    )
    (net (code "71") (name "~{FRAM_CS}") (class "Default")
      (node (ref "R6") (pin "1") (pinfunction "1_1") (pintype "passive"))
      (node (ref "U2") (pin "1") (pinfunction "~{CS}_1") (pintype "bidirectional"))
      (node (ref "U3") (pin "44") (pinfunction "P5.0/STE1_44") (pintype "bidirectional"))
    )
    (net (code "72") (name "~{FRAM_HOLD}") (class "Default")
      (node (ref "R4") (pin "1") (pinfunction "1_1") (pintype "passive"))
      (node (ref "U2") (pin "7") (pinfunction "~{HOLD}_7") (pintype "bidirectional"))
      (node (ref "U3") (pin "51") (pinfunction "P5.7/TBOUTH/SVSOUT_51") (pintype "bidirectional"))
    )
    (net (code "73") (name "~{FRAM_WP}") (class "Default")
      (node (ref "R5") (pin "1") (pinfunction "1_1") (pintype "passive"))
      (node (ref "U2") (pin "3") (pinfunction "~{WP}_3") (pintype "bidirectional"))
      (node (ref "U3") (pin "32") (pinfunction "P3.4/UTXD0_32") (pintype "bidirectional"))
    )
    (net (code "74") (name "~{RADIO_CS}") (class "Default")
      (node (ref "R13") (pin "2") (pinfunction "2_2") (pintype "passive"))
      (node (ref "U3") (pin "38") (pinfunction "P4.2/TB2_38") (pintype "bidirectional"))
      (node (ref "U4") (pin "31") (pinfunction "CSN_31") (pintype "bidirectional"))
    )
    (net (code "75") (name "~{RADIO_RESET}") (class "Default")
      (node (ref "R11") (pin "1") (pinfunction "1_1") (pintype "passive"))
      (node (ref "U3") (pin "42") (pinfunction "P4.6/TB6_42") (pintype "bidirectional"))
      (node (ref "U4") (pin "21") (pinfunction "RESETN_21") (pintype "bidirectional"))
    )
    (net (code "76") (name "~{RESET}") (class "Default")
      (node (ref "C14") (pin "1") (pinfunction "1_1") (pintype "bidirectional"))
      (node (ref "J2") (pin "6") (pinfunction "RST#_6") (pintype "bidirectional"))
      (node (ref "R9") (pin "2") (pinfunction "2_2") (pintype "passive"))
      (node (ref "U3") (pin "58") (pinfunction "RST/NMI_58") (pintype "bidirectional"))
    )
  )
)
